# Sheet2.net
KiCad netlist of a schematic drawn in Altium Designer
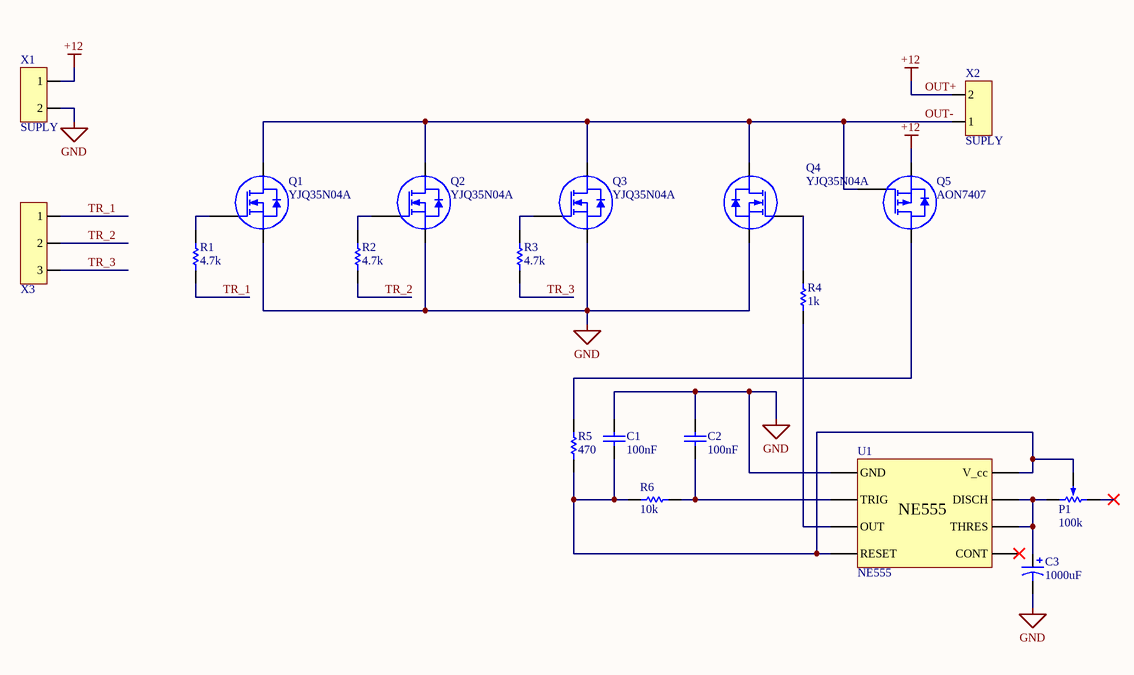
[diagram p0: Sheet2.SchDoc]

(export (version "E")
  (design (tool "Eeschema 10.0.6"))
  (components
    (comp (ref "C1")
      (value "Capacitor")
      (footprint "CAP_0603")
      (fields (field (name "CAPACITANCE") "100nF"))
      (libsource (lib "COMPONENTS_2022") (part "Capacitor"))
    )
    (comp (ref "C2")
      (value "Capacitor")
      (footprint "CAP_0603")
      (fields (field (name "CAPACITANCE") "100nF"))
      (libsource (lib "COMPONENTS_2022") (part "Capacitor"))
    )
    (comp (ref "C3")
      (value "1000uF")
      (footprint "CAP_POL_12.5x20")
      (fields (field (name "Comment") "Capacitor_Pol"))
      (libsource (lib "COMPONENTS_2022") (part "Capacitor_Pol"))
    )
    (comp (ref "P1")
      (value "Potentiometer")
      (footprint "3296w")
      (fields (field (name "RESISTANCE") "100k"))
      (libsource (lib "COMPONENTS_2022") (part "Potentiometer"))
    )
    (comp (ref "Q1")
      (value "YJQ35N04A")
      (footprint "DFN3.3x3.3")
      (libsource (lib "COMPONENTS_2022") (part "YJQ35N04A"))
    )
    (comp (ref "Q2")
      (value "YJQ35N04A")
      (footprint "DFN3.3x3.3")
      (libsource (lib "COMPONENTS_2022") (part "YJQ35N04A"))
    )
    (comp (ref "Q3")
      (value "YJQ35N04A")
      (footprint "DFN3.3x3.3")
      (libsource (lib "COMPONENTS_2022") (part "YJQ35N04A"))
    )
    (comp (ref "Q4")
      (value "YJQ35N04A")
      (footprint "DFN3.3x3.3")
      (libsource (lib "COMPONENTS_2022") (part "YJQ35N04A"))
    )
    (comp (ref "Q5")
      (value "AON7407")
      (footprint "DFN3x3")
      (libsource (lib "COMPONENTS_2022") (part "AON7407"))
    )
    (comp (ref "R1")
      (value "Resistor")
      (footprint "RES_0603")
      (fields (field (name "RESISTANCE") "4.7k"))
      (libsource (lib "COMPONENTS_2022") (part "Resistor"))
    )
    (comp (ref "R2")
      (value "Resistor")
      (footprint "RES_0603")
      (fields (field (name "RESISTANCE") "4.7k"))
      (libsource (lib "COMPONENTS_2022") (part "Resistor"))
    )
    (comp (ref "R3")
      (value "Resistor")
      (footprint "RES_0603")
      (fields (field (name "RESISTANCE") "4.7k"))
      (libsource (lib "COMPONENTS_2022") (part "Resistor"))
    )
    (comp (ref "R4")
      (value "Resistor")
      (footprint "RES_0603")
      (fields (field (name "RESISTANCE") "1k"))
      (libsource (lib "COMPONENTS_2022") (part "Resistor"))
    )
    (comp (ref "R5")
      (value "Resistor")
      (footprint "RES_0603")
      (fields (field (name "RESISTANCE") "470"))
      (libsource (lib "COMPONENTS_2022") (part "Resistor"))
    )
    (comp (ref "R6")
      (value "Resistor")
      (footprint "RES_0603")
      (fields (field (name "RESISTANCE") "10k"))
      (libsource (lib "COMPONENTS_2022") (part "Resistor"))
    )
    (comp (ref "U1") (value "NE555") (footprint "SO8") (libsource (lib "COMPONENTS_2022") (part "NE555")))
    (comp (ref "X1")
      (value "SUPLY")
      (footprint "SCREW_TERMINAL_X2 5mm")
      (libsource (lib "COMPONENTS_2022") (part "Double connector"))
    )
    (comp (ref "X2")
      (value "SUPLY")
      (footprint "SCREW_TERMINAL_X2 5mm")
      (libsource (lib "") (part "Double connector_1"))
    )
    (comp (ref "X3")
      (value "?")
      (footprint "SCREW_TERMINAL_X3 5mm")
      (libsource (lib "COMPONENTS_2022") (part "Tripple Connecotr"))
    )
  )
  (nets
    (net (code "1") (name "+12") (class "Default")
      (node (ref "Q5") (pin "1") (pinfunction "S_1") (pintype "passive"))
      (node (ref "X1") (pin "1") (pinfunction "1_1") (pintype "passive"))
      (node (ref "X2") (pin "2") (pinfunction "2_2") (pintype "passive"))
    )
    (net (code "2") (name "/OUT-") (class "Default")
      (node (ref "Q1") (pin "5") (pinfunction "D_5") (pintype "passive"))
      (node (ref "Q2") (pin "5") (pinfunction "D_5") (pintype "passive"))
      (node (ref "Q3") (pin "5") (pinfunction "D_5") (pintype "passive"))
      (node (ref "Q4") (pin "5") (pinfunction "D_5") (pintype "passive"))
      (node (ref "Q5") (pin "4") (pinfunction "G_4") (pintype "passive"))
      (node (ref "X2") (pin "1") (pinfunction "1_1") (pintype "passive"))
    )
    (net (code "3") (name "/TR_1") (class "Default")
      (node (ref "R1") (pin "1") (pinfunction "1_1") (pintype "passive"))
      (node (ref "X3") (pin "1") (pinfunction "1_1") (pintype "passive"))
    )
    (net (code "4") (name "/TR_2") (class "Default")
      (node (ref "R2") (pin "1") (pinfunction "1_1") (pintype "passive"))
      (node (ref "X3") (pin "2") (pinfunction "2_2") (pintype "passive"))
    )
    (net (code "5") (name "/TR_3") (class "Default")
      (node (ref "R3") (pin "1") (pinfunction "1_1") (pintype "passive"))
      (node (ref "X3") (pin "3") (pinfunction "3_3") (pintype "passive"))
    )
    (net (code "6") (name "GND") (class "Default")
      (node (ref "C1") (pin "1") (pinfunction "1_1") (pintype "passive"))
      (node (ref "C2") (pin "2") (pinfunction "2_2") (pintype "passive"))
      (node (ref "C3") (pin "2") (pinfunction "2_2") (pintype "passive"))
      (node (ref "Q1") (pin "1") (pinfunction "S_1") (pintype "passive"))
      (node (ref "Q2") (pin "1") (pinfunction "S_1") (pintype "passive"))
      (node (ref "Q3") (pin "1") (pinfunction "S_1") (pintype "passive"))
      (node (ref "Q4") (pin "1") (pinfunction "S_1") (pintype "passive"))
      (node (ref "U1") (pin "1") (pinfunction "GND_1") (pintype "passive"))
      (node (ref "X1") (pin "2") (pinfunction "2_2") (pintype "passive"))
    )
    (net (code "7") (name "Net-(Q1-G)") (class "Default")
      (node (ref "Q1") (pin "4") (pinfunction "G_4") (pintype "passive"))
      (node (ref "R1") (pin "2") (pinfunction "2_2") (pintype "passive"))
    )
    (net (code "8") (name "Net-(Q2-G)") (class "Default")
      (node (ref "Q2") (pin "4") (pinfunction "G_4") (pintype "passive"))
      (node (ref "R2") (pin "2") (pinfunction "2_2") (pintype "passive"))
    )
    (net (code "9") (name "Net-(Q3-G)") (class "Default")
      (node (ref "Q3") (pin "4") (pinfunction "G_4") (pintype "passive"))
      (node (ref "R3") (pin "2") (pinfunction "2_2") (pintype "passive"))
    )
    (net (code "10") (name "Net-(Q4-G)") (class "Default")
      (node (ref "Q4") (pin "4") (pinfunction "G_4") (pintype "passive"))
      (node (ref "R4") (pin "1") (pinfunction "1_1") (pintype "passive"))
    )
    (net (code "11") (name "Net-(Q5-D)") (class "Default")
      (node (ref "Q5") (pin "5") (pinfunction "D_5") (pintype "passive"))
      (node (ref "R5") (pin "2") (pinfunction "2_2") (pintype "passive"))
    )
    (net (code "12") (name "Net-(U1-DISCH)") (class "Default")
      (node (ref "C3") (pin "1") (pinfunction "1_1") (pintype "passive"))
      (node (ref "P1") (pin "1") (pinfunction "1_1") (pintype "passive"))
      (node (ref "U1") (pin "6") (pinfunction "THRES_6") (pintype "passive"))
      (node (ref "U1") (pin "7") (pinfunction "DISCH_7") (pintype "passive"))
    )
    (net (code "13") (name "Net-(U1-OUT)") (class "Default")
      (node (ref "R4") (pin "2") (pinfunction "2_2") (pintype "passive"))
      (node (ref "U1") (pin "3") (pinfunction "OUT_3") (pintype "passive"))
    )
    (net (code "14") (name "Net-(U1-RESET)") (class "Default")
      (node (ref "C1") (pin "2") (pinfunction "2_2") (pintype "passive"))
      (node (ref "P1") (pin "2") (pinfunction "2_2") (pintype "passive"))
      (node (ref "R5") (pin "1") (pinfunction "1_1") (pintype "passive"))
      (node (ref "R6") (pin "1") (pinfunction "1_1") (pintype "passive"))
      (node (ref "U1") (pin "4") (pinfunction "RESET_4") (pintype "passive"))
      (node (ref "U1") (pin "8") (pinfunction "V_cc_8") (pintype "passive"))
    )
    (net (code "15") (name "Net-(U1-TRIG)") (class "Default")
      (node (ref "C2") (pin "1") (pinfunction "1_1") (pintype "passive"))
      (node (ref "R6") (pin "2") (pinfunction "2_2") (pintype "passive"))
      (node (ref "U1") (pin "2") (pinfunction "TRIG_2") (pintype "passive"))
    )
    (net (code "16") (name "unconnected-(P1-Pad3)") (class "Default")
      (node (ref "P1") (pin "3") (pinfunction "3_3") (pintype "passive+no_connect"))
    )
    (net (code "17") (name "unconnected-(U1-CONT-Pad5)") (class "Default")
      (node (ref "U1") (pin "5") (pinfunction "CONT_5") (pintype "passive+no_connect"))
    )
  )
)
